# generator.net
KiCad netlist of a schematic drawn in EAGLE
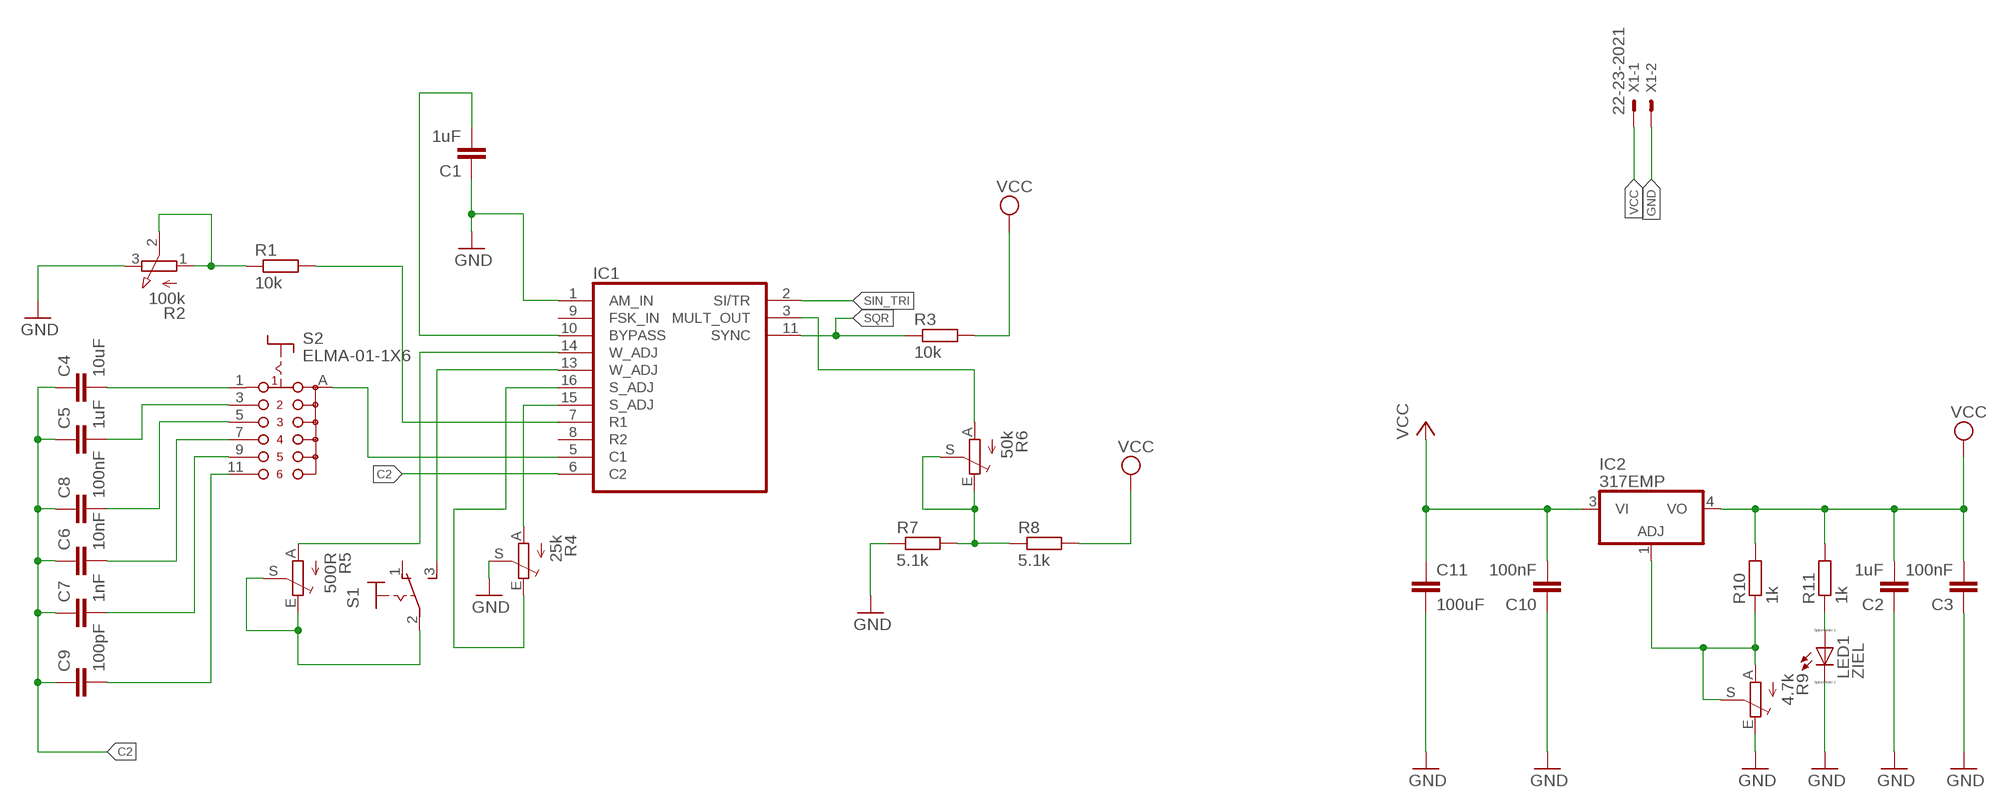
[diagram p0: schematic, sheet 1]

(export (version "E")
  (design (tool "Eeschema 10.0.6"))
  (components
    (comp (ref "C1")
      (value "1uF")
      (footprint "eagle-import:C0805")
      (libsource (lib "eagle-import") (part "C-EUC0805"))
    )
    (comp (ref "C2")
      (value "1uF")
      (footprint "eagle-import:C0805")
      (libsource (lib "eagle-import") (part "C-EUC0805"))
    )
    (comp (ref "C3")
      (value "100nF")
      (footprint "eagle-import:C0805")
      (libsource (lib "eagle-import") (part "C-EUC0805"))
    )
    (comp (ref "C4")
      (value "10uF")
      (footprint "eagle-import:C0805")
      (libsource (lib "eagle-import") (part "C-EUC0805"))
    )
    (comp (ref "C5")
      (value "1uF")
      (footprint "eagle-import:C0805")
      (libsource (lib "eagle-import") (part "C-EUC0805"))
    )
    (comp (ref "C6")
      (value "10nF")
      (footprint "eagle-import:C0805")
      (libsource (lib "eagle-import") (part "C-EUC0805"))
    )
    (comp (ref "C7")
      (value "1nF")
      (footprint "eagle-import:C0805")
      (libsource (lib "eagle-import") (part "C-EUC0805"))
    )
    (comp (ref "C8")
      (value "100nF")
      (footprint "eagle-import:C0805")
      (libsource (lib "eagle-import") (part "C-EUC0805"))
    )
    (comp (ref "C9")
      (value "100pF")
      (footprint "eagle-import:C0805")
      (libsource (lib "eagle-import") (part "C-EUC0805"))
    )
    (comp (ref "C10")
      (value "100nF")
      (footprint "eagle-import:C0805")
      (libsource (lib "eagle-import") (part "C-EUC0805"))
    )
    (comp (ref "C11")
      (value "100uF")
      (footprint "eagle-import:C0805")
      (libsource (lib "eagle-import") (part "C-EUC0805"))
    )
    (comp (ref "IC1")
      (value "XR-2206")
      (footprint "eagle-import:DIL16")
      (libsource (lib "eagle-import") (part "XR-2206"))
    )
    (comp (ref "IC2")
      (value "317EMP")
      (footprint "eagle-import:SOT223")
      (libsource (lib "eagle-import") (part "317EMP"))
    )
    (comp (ref "LED1")
      (value "ZIEL")
      (footprint "eagle-import:LED_1206")
      (libsource (lib "eagle-import") (part "LED_E"))
    )
    (comp (ref "R1")
      (value "10k")
      (footprint "eagle-import:R0805")
      (libsource (lib "eagle-import") (part "R-EU_R0805"))
    )
    (comp (ref "R2")
      (value "100k")
      (footprint "eagle-import:3RP_1610N")
      (libsource (lib "eagle-import") (part "3RP/1610N"))
    )
    (comp (ref "R3")
      (value "10k")
      (footprint "eagle-import:R0805")
      (libsource (lib "eagle-import") (part "R-EU_R0805"))
    )
    (comp (ref "R4")
      (value "25k")
      (footprint "eagle-import:PT-SPIN")
      (libsource (lib "eagle-import") (part "TRIM_EU-PTSPIN"))
    )
    (comp (ref "R5")
      (value "500R")
      (footprint "eagle-import:PT-SPIN")
      (libsource (lib "eagle-import") (part "TRIM_EU-PTSPIN"))
    )
    (comp (ref "R6")
      (value "50k")
      (footprint "eagle-import:PT-SPIN")
      (libsource (lib "eagle-import") (part "TRIM_EU-PTSPIN"))
    )
    (comp (ref "R7")
      (value "5.1k")
      (footprint "eagle-import:R0805")
      (libsource (lib "eagle-import") (part "R-EU_R0805"))
    )
    (comp (ref "R8")
      (value "5.1k")
      (footprint "eagle-import:R0805")
      (libsource (lib "eagle-import") (part "R-EU_R0805"))
    )
    (comp (ref "R9")
      (value "4.7k")
      (footprint "eagle-import:PT-SPIN")
      (libsource (lib "eagle-import") (part "TRIM_EU-PTSPIN"))
    )
    (comp (ref "R10")
      (value "1k")
      (footprint "eagle-import:R0805")
      (libsource (lib "eagle-import") (part "R-EU_R0805"))
    )
    (comp (ref "R11")
      (value "1k")
      (footprint "eagle-import:R0805")
      (libsource (lib "eagle-import") (part "R-EU_R0805"))
    )
    (comp (ref "S1")
      (value "320-916")
      (footprint "eagle-import:320-916")
      (libsource (lib "eagle-import") (part "320-916"))
    )
    (comp (ref "S2")
      (value "ELMA-01-1X6")
      (footprint "eagle-import:ELMA-01-1X6")
      (libsource (lib "eagle-import") (part "ELMA-01-1X6"))
    )
    (comp (ref "X1")
      (value "22-23-2021")
      (footprint "eagle-import:22-23-2021")
      (fields (field (name "MF") "MOLEX"))
      (libsource (lib "eagle-import") (part "22-23-2021"))
    )
  )
  (nets
    (net (code "1") (name "C2") (class "Default")
      (node (ref "C4") (pin "1") (pinfunction "1_1") (pintype "passive"))
      (node (ref "C5") (pin "1") (pinfunction "1_1") (pintype "passive"))
      (node (ref "C6") (pin "1") (pinfunction "1_1") (pintype "passive"))
      (node (ref "C7") (pin "1") (pinfunction "1_1") (pintype "passive"))
      (node (ref "C8") (pin "1") (pinfunction "1_1") (pintype "passive"))
      (node (ref "C9") (pin "1") (pinfunction "1_1") (pintype "passive"))
      (node (ref "IC1") (pin "6") (pinfunction "C2_6") (pintype "input"))
    )
    (net (code "2") (name "GND") (class "Default")
      (node (ref "C1") (pin "1") (pinfunction "1_1") (pintype "passive"))
      (node (ref "C10") (pin "1") (pinfunction "1_1") (pintype "passive"))
      (node (ref "C11") (pin "2") (pinfunction "2_2") (pintype "passive"))
      (node (ref "C2") (pin "1") (pinfunction "1_1") (pintype "passive"))
      (node (ref "C3") (pin "1") (pinfunction "1_1") (pintype "passive"))
      (node (ref "IC1") (pin "1") (pinfunction "AM_IN_1") (pintype "input"))
      (node (ref "LED1") (pin "C") (pinfunction "C_C") (pintype "passive"))
      (node (ref "R2") (pin "3") (pinfunction "E_3") (pintype "passive"))
      (node (ref "R4") (pin "S") (pinfunction "S_S") (pintype "passive"))
      (node (ref "R7") (pin "1") (pinfunction "1_1") (pintype "passive"))
      (node (ref "R9") (pin "E") (pinfunction "E_E") (pintype "passive"))
      (node (ref "X1") (pin "2") (pinfunction "S_2") (pintype "passive"))
    )
    (net (code "3") (name "Net-(C4-Pad2)") (class "Default")
      (node (ref "C4") (pin "2") (pinfunction "2_2") (pintype "passive"))
      (node (ref "S2") (pin "1") (pinfunction "1_1") (pintype "passive"))
    )
    (net (code "4") (name "Net-(IC1A-BYPASS)") (class "Default")
      (node (ref "C1") (pin "2") (pinfunction "2_2") (pintype "passive"))
      (node (ref "IC1") (pin "10") (pinfunction "BYPASS_10") (pintype "input"))
    )
    (net (code "5") (name "Net-(IC1A-C1)") (class "Default")
      (node (ref "IC1") (pin "5") (pinfunction "C1_5") (pintype "input"))
      (node (ref "S2") (pin "A") (pinfunction "S_A") (pintype "passive"))
    )
    (net (code "6") (name "Net-(IC1A-MULT_OUT)") (class "Default")
      (node (ref "IC1") (pin "3") (pinfunction "MULT_OUT_3") (pintype "output"))
      (node (ref "R6") (pin "A") (pinfunction "A_A") (pintype "passive"))
    )
    (net (code "7") (name "Net-(IC1A-R1)") (class "Default")
      (node (ref "IC1") (pin "7") (pinfunction "R1_7") (pintype "input"))
      (node (ref "R1") (pin "2") (pinfunction "2_2") (pintype "passive"))
    )
    (net (code "8") (name "Net-(IC1A-S_ADJ-Pad15)") (class "Default")
      (node (ref "IC1") (pin "15") (pinfunction "S_ADJ_15") (pintype "input"))
      (node (ref "R4") (pin "A") (pinfunction "A_A") (pintype "passive"))
    )
    (net (code "9") (name "Net-(IC1A-S_ADJ-Pad16)") (class "Default")
      (node (ref "IC1") (pin "16") (pinfunction "S_ADJ_16") (pintype "input"))
      (node (ref "R4") (pin "E") (pinfunction "E_E") (pintype "passive"))
    )
    (net (code "10") (name "Net-(IC1A-W_ADJ-Pad14)") (class "Default")
      (node (ref "IC1") (pin "14") (pinfunction "W_ADJ_14") (pintype "input"))
      (node (ref "R5") (pin "A") (pinfunction "A_A") (pintype "passive"))
    )
    (net (code "11") (name "Net-(IC2-ADJ)") (class "Default")
      (node (ref "IC2") (pin "1") (pinfunction "ADJ_1") (pintype "input"))
      (node (ref "R10") (pin "1") (pinfunction "1_1") (pintype "passive"))
      (node (ref "R9") (pin "A") (pinfunction "A_A") (pintype "passive"))
      (node (ref "R9") (pin "S") (pinfunction "S_S") (pintype "passive"))
    )
    (net (code "12") (name "Net-(LED1-PadA)") (class "Default")
      (node (ref "LED1") (pin "A") (pinfunction "A_A") (pintype "passive"))
      (node (ref "R11") (pin "1") (pinfunction "1_1") (pintype "passive"))
    )
    (net (code "13") (name "Net-(R2-A)") (class "Default")
      (node (ref "R1") (pin "1") (pinfunction "1_1") (pintype "passive"))
      (node (ref "R2") (pin "1") (pinfunction "A_1") (pintype "passive"))
      (node (ref "R2") (pin "2") (pinfunction "S_2") (pintype "passive"))
    )
    (net (code "14") (name "Net-(R6-PadE)") (class "Default")
      (node (ref "R6") (pin "E") (pinfunction "E_E") (pintype "passive"))
      (node (ref "R6") (pin "S") (pinfunction "S_S") (pintype "passive"))
      (node (ref "R7") (pin "2") (pinfunction "2_2") (pintype "passive"))
      (node (ref "R8") (pin "1") (pinfunction "1_1") (pintype "passive"))
    )
    (net (code "15") (name "Net-(S1-P)") (class "Default")
      (node (ref "R5") (pin "E") (pinfunction "E_E") (pintype "passive"))
      (node (ref "R5") (pin "S") (pinfunction "S_S") (pintype "passive"))
      (node (ref "S1") (pin "2") (pinfunction "P_2") (pintype "passive"))
    )
    (net (code "16") (name "Net-(S1-S)") (class "Default")
      (node (ref "IC1") (pin "13") (pinfunction "W_ADJ_13") (pintype "input"))
      (node (ref "S1") (pin "3") (pinfunction "S_3") (pintype "passive"))
    )
    (net (code "17") (name "Net-(S2-2)") (class "Default")
      (node (ref "C5") (pin "2") (pinfunction "2_2") (pintype "passive"))
      (node (ref "S2") (pin "3") (pinfunction "2_3") (pintype "passive"))
    )
    (net (code "18") (name "Net-(S2-3)") (class "Default")
      (node (ref "C8") (pin "2") (pinfunction "2_2") (pintype "passive"))
      (node (ref "S2") (pin "5") (pinfunction "3_5") (pintype "passive"))
    )
    (net (code "19") (name "Net-(S2-4)") (class "Default")
      (node (ref "C6") (pin "2") (pinfunction "2_2") (pintype "passive"))
      (node (ref "S2") (pin "7") (pinfunction "4_7") (pintype "passive"))
    )
    (net (code "20") (name "Net-(S2-5)") (class "Default")
      (node (ref "C7") (pin "2") (pinfunction "2_2") (pintype "passive"))
      (node (ref "S2") (pin "9") (pinfunction "5_9") (pintype "passive"))
    )
    (net (code "21") (name "Net-(S2-6)") (class "Default")
      (node (ref "C9") (pin "2") (pinfunction "2_2") (pintype "passive"))
      (node (ref "S2") (pin "11") (pinfunction "6_11") (pintype "passive"))
    )
    (net (code "22") (name "SIN_TRI") (class "Default")
      (node (ref "IC1") (pin "2") (pinfunction "SI/TR_2") (pintype "output"))
    )
    (net (code "23") (name "SQR") (class "Default")
      (node (ref "IC1") (pin "11") (pinfunction "SYNC_11") (pintype "output"))
      (node (ref "R3") (pin "1") (pinfunction "1_1") (pintype "passive"))
    )
    (net (code "24") (name "VCC") (class "Default")
      (node (ref "C10") (pin "2") (pinfunction "2_2") (pintype "passive"))
      (node (ref "C11") (pin "1") (pinfunction "1_1") (pintype "passive"))
      (node (ref "C2") (pin "2") (pinfunction "2_2") (pintype "passive"))
      (node (ref "C3") (pin "2") (pinfunction "2_2") (pintype "passive"))
      (node (ref "IC2") (pin "3") (pinfunction "VI_3") (pintype "input"))
      (node (ref "IC2") (pin "4") (pinfunction "VO_4") (pintype "passive"))
      (node (ref "R10") (pin "2") (pinfunction "2_2") (pintype "passive"))
      (node (ref "R11") (pin "2") (pinfunction "2_2") (pintype "passive"))
      (node (ref "R3") (pin "2") (pinfunction "2_2") (pintype "passive"))
      (node (ref "R8") (pin "2") (pinfunction "2_2") (pintype "passive"))
      (node (ref "X1") (pin "1") (pinfunction "S_1") (pintype "passive"))
    )
    (net (code "25") (name "unconnected-(IC1A-FSK_IN-Pad9)") (class "Default")
      (node (ref "IC1") (pin "9") (pinfunction "FSK_IN_9") (pintype "input"))
    )
    (net (code "26") (name "unconnected-(IC1A-R2-Pad8)") (class "Default")
      (node (ref "IC1") (pin "8") (pinfunction "R2_8") (pintype "input"))
    )
    (net (code "27") (name "unconnected-(S1-O-Pad1)") (class "Default")
      (node (ref "S1") (pin "1") (pinfunction "O_1") (pintype "passive"))
    )
  )
)
